# oled_block.net
KiCad netlist of a schematic drawn in EAGLE
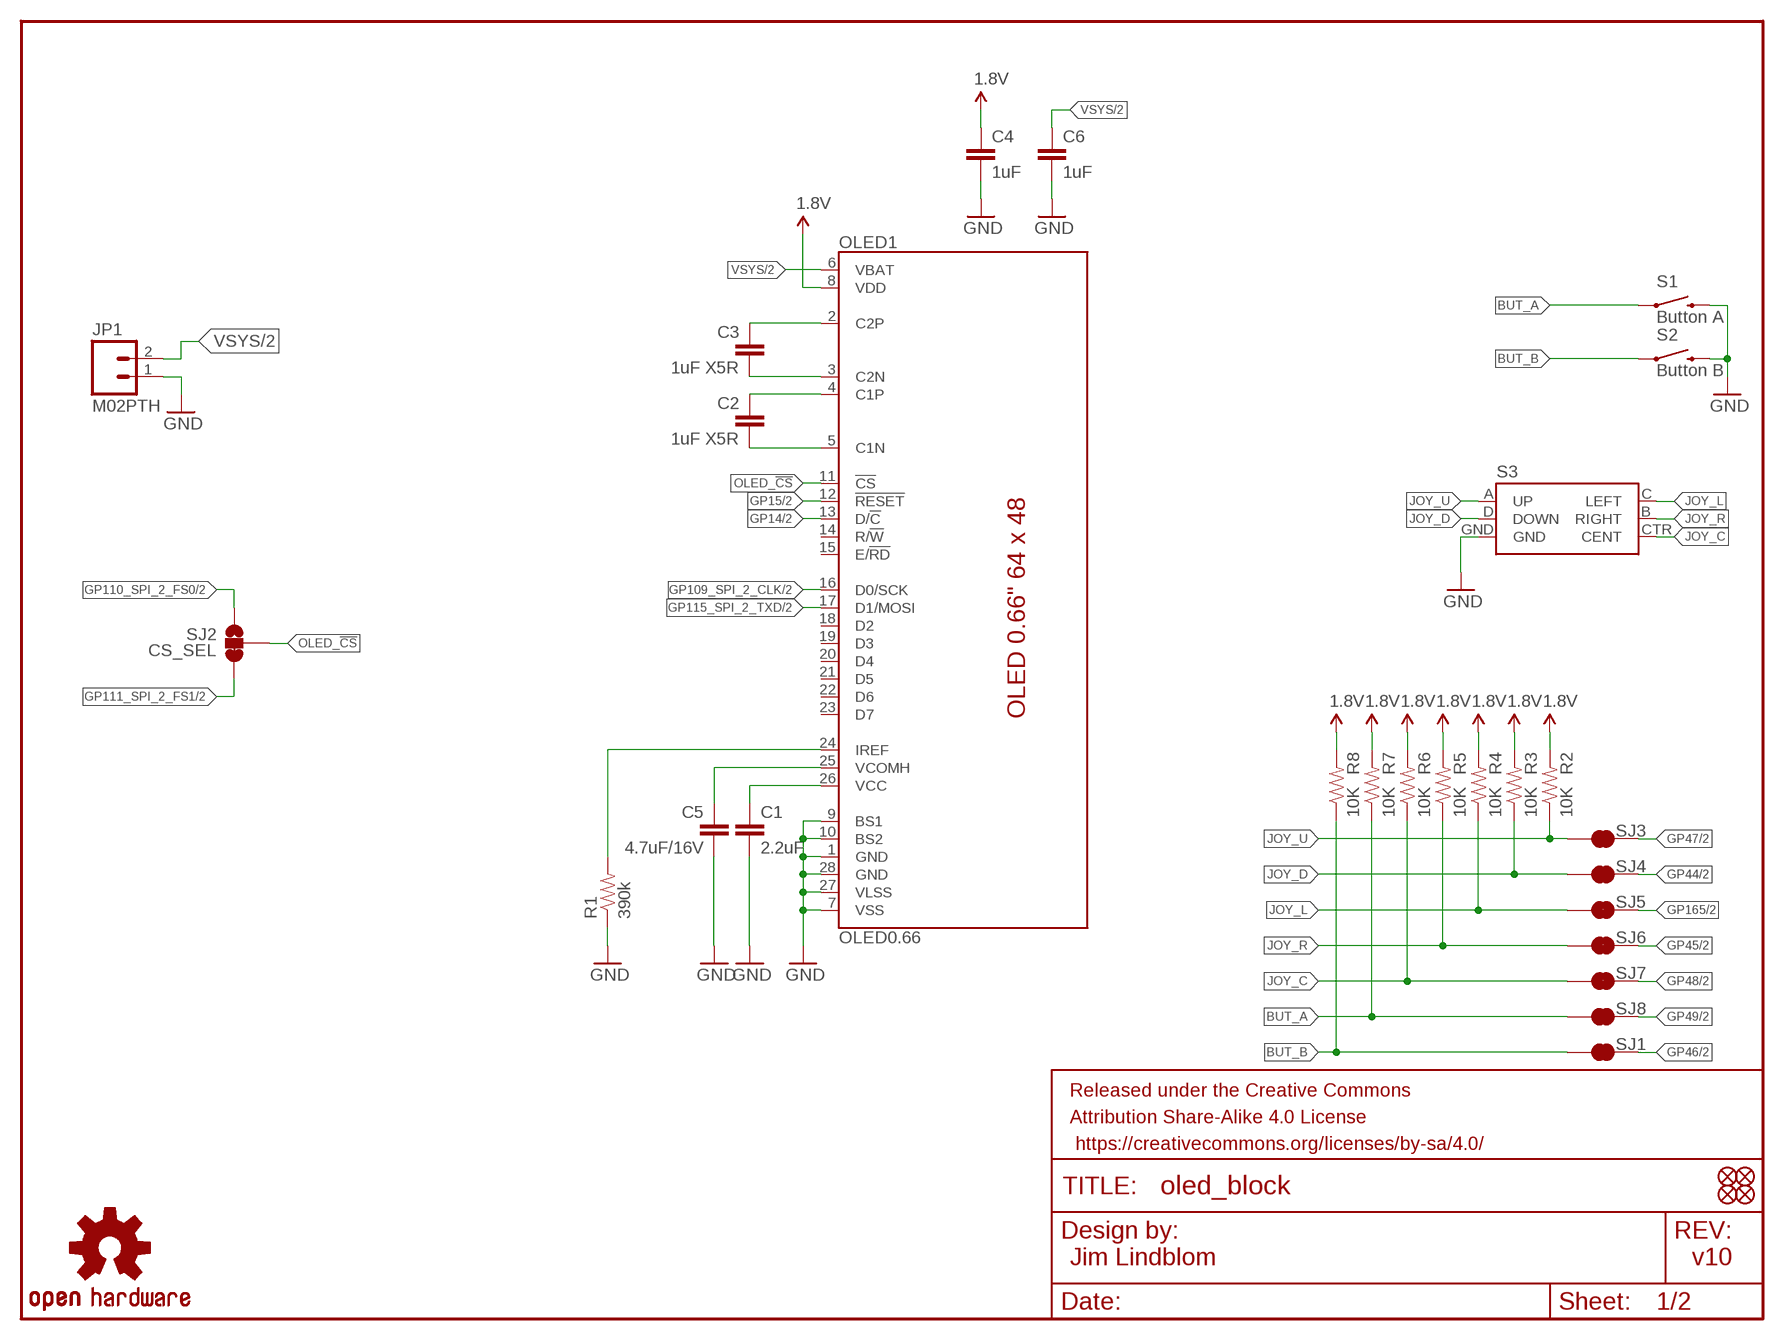
[diagram p0: schematic, sheet 1]
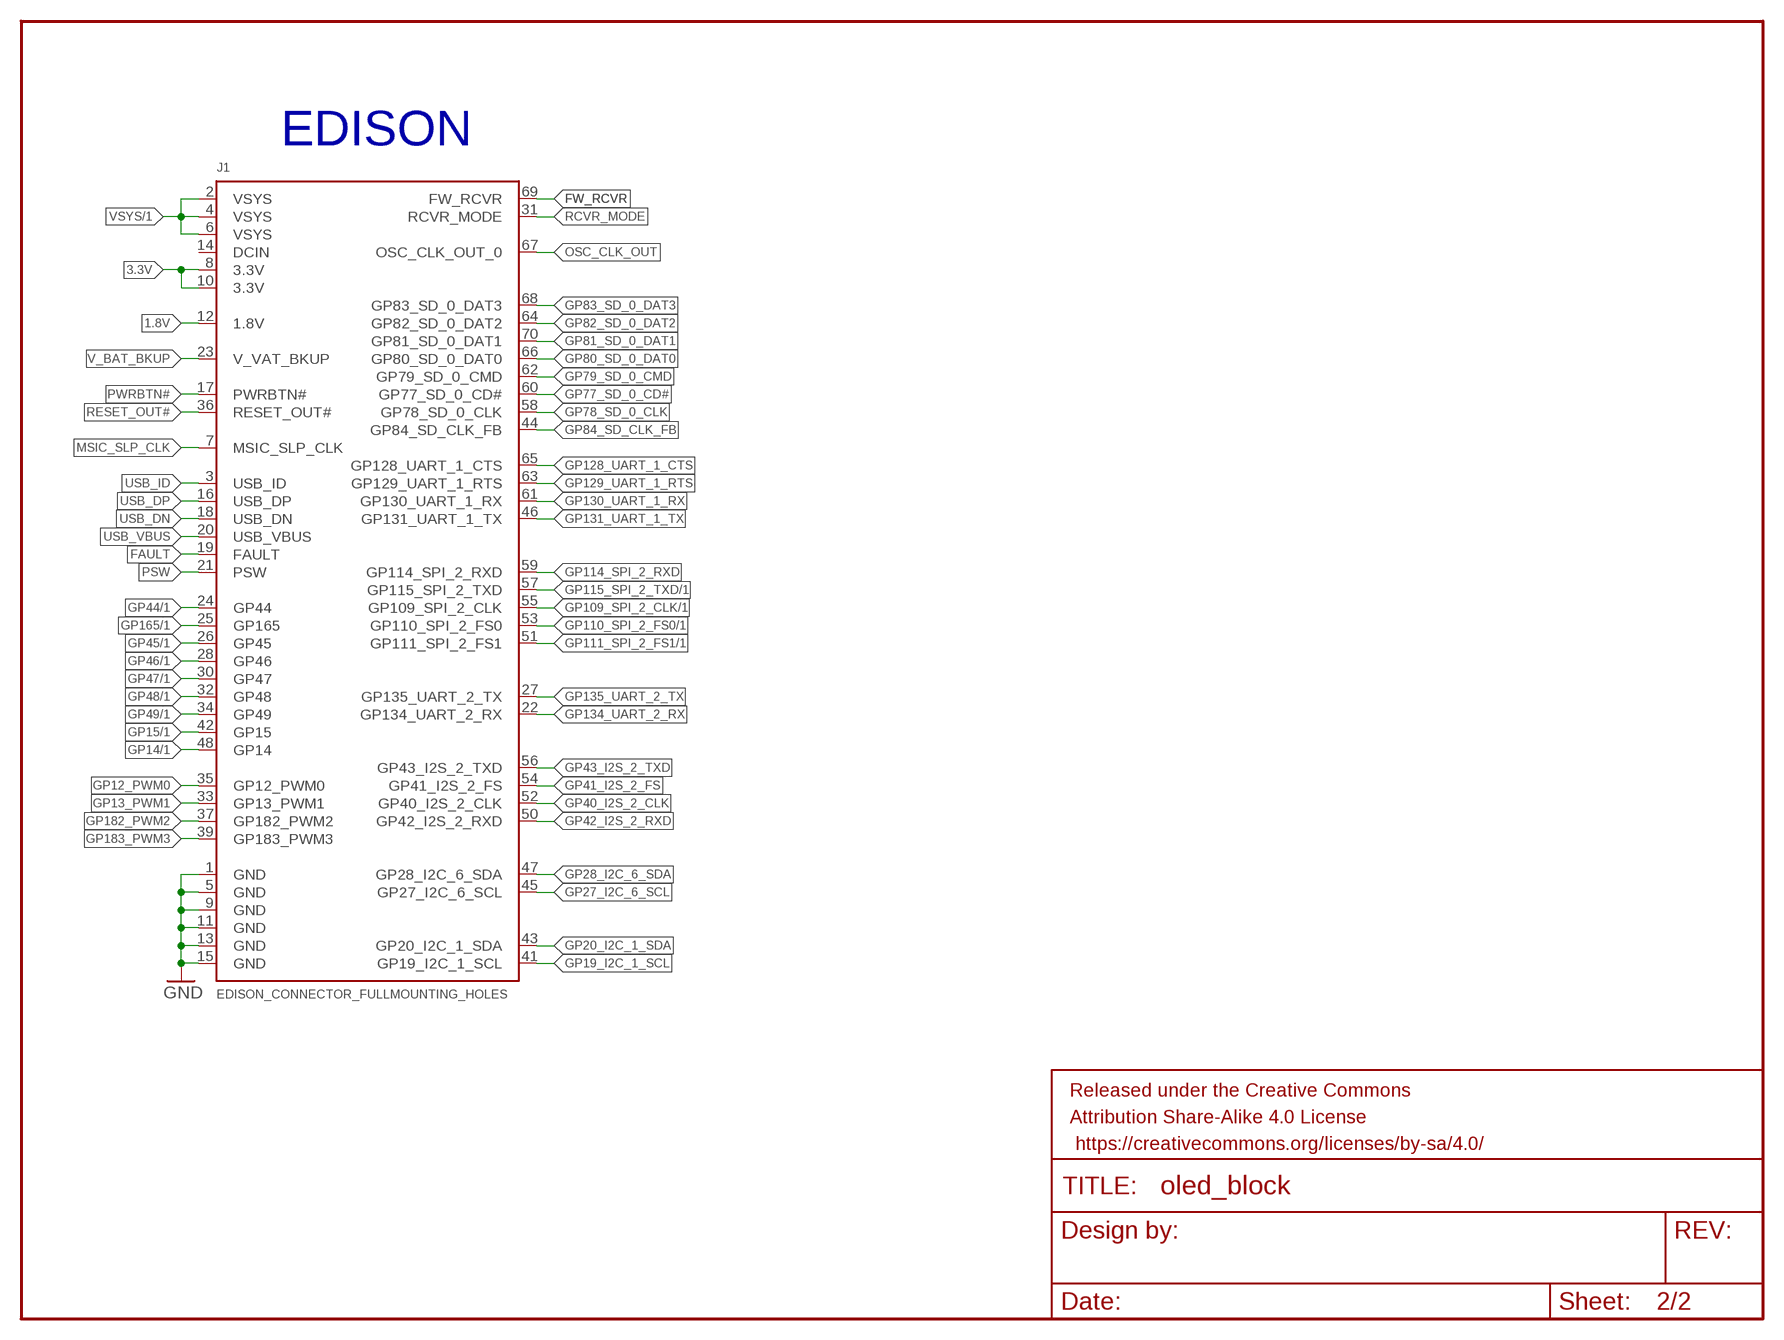
[diagram p1: schematic, sheet 2]

(export (version "E")
  (design (tool "Eeschema 10.0.6"))
  (components
    (comp (ref "C1")
      (value "2.2uF")
      (footprint "eagle-import:0805")
      (libsource (lib "eagle-import") (part "CAP0805"))
    )
    (comp (ref "C2")
      (value "1uF X5R")
      (footprint "eagle-import:0805")
      (libsource (lib "eagle-import") (part "CAP0805"))
    )
    (comp (ref "C3")
      (value "1uF X5R")
      (footprint "eagle-import:0805")
      (libsource (lib "eagle-import") (part "CAP0805"))
    )
    (comp (ref "C4")
      (value "1uF")
      (footprint "eagle-import:0603-CAP")
      (libsource (lib "eagle-import") (part "CAP0603-CAP"))
    )
    (comp (ref "C5")
      (value "4.7uF/16V")
      (footprint "eagle-import:1206")
      (libsource (lib "eagle-import") (part "CAP1206"))
    )
    (comp (ref "C6")
      (value "1uF")
      (footprint "eagle-import:0603-CAP")
      (libsource (lib "eagle-import") (part "CAP0603-CAP"))
    )
    (comp (ref "FID1")
      (value "FIDUCIAL1X2")
      (footprint "eagle-import:FIDUCIAL-1X2")
      (libsource (lib "eagle-import") (part "FIDUCIAL1X2"))
    )
    (comp (ref "FID2")
      (value "FIDUCIAL1X2")
      (footprint "eagle-import:FIDUCIAL-1X2")
      (libsource (lib "eagle-import") (part "FIDUCIAL1X2"))
    )
    (comp (ref "FID3")
      (value "FIDUCIAL1X2")
      (footprint "eagle-import:FIDUCIAL-1X2")
      (libsource (lib "eagle-import") (part "FIDUCIAL1X2"))
    )
    (comp (ref "FID4")
      (value "FIDUCIAL1X2")
      (footprint "eagle-import:FIDUCIAL-1X2")
      (libsource (lib "eagle-import") (part "FIDUCIAL1X2"))
    )
    (comp (ref "FRAME1")
      (value "FRAME-LETTER")
      (footprint "eagle-import:CREATIVE_COMMONS")
      (libsource (lib "eagle-import") (part "FRAME-LETTER"))
    )
    (comp (ref "JP1")
      (value "M02PTH")
      (footprint "eagle-import:1X02")
      (libsource (lib "eagle-import") (part "M02PTH"))
    )
    (comp (ref "LOGO2")
      (value "OSHW-LOGOS")
      (footprint "eagle-import:OSHW-LOGO-S")
      (libsource (lib "eagle-import") (part "OSHW-LOGOS"))
    )
    (comp (ref "OLED1")
      (value "OLED0.66")
      (footprint "eagle-import:OLED-0.66-64X48")
      (libsource (lib "eagle-import") (part "OLED0.66"))
    )
    (comp (ref "R1")
      (value "390k")
      (footprint "eagle-import:0603-RES")
      (libsource (lib "eagle-import") (part "RESISTOR0603-RES"))
    )
    (comp (ref "R2")
      (value "10K")
      (footprint "eagle-import:0603-RES")
      (libsource (lib "eagle-import") (part "10KOHM1/10W1%(0603)0603"))
    )
    (comp (ref "R3")
      (value "10K")
      (footprint "eagle-import:0603-RES")
      (libsource (lib "eagle-import") (part "10KOHM1/10W1%(0603)0603"))
    )
    (comp (ref "R4")
      (value "10K")
      (footprint "eagle-import:0603-RES")
      (libsource (lib "eagle-import") (part "10KOHM1/10W1%(0603)0603"))
    )
    (comp (ref "R5")
      (value "10K")
      (footprint "eagle-import:0603-RES")
      (libsource (lib "eagle-import") (part "10KOHM1/10W1%(0603)0603"))
    )
    (comp (ref "R6")
      (value "10K")
      (footprint "eagle-import:0603-RES")
      (libsource (lib "eagle-import") (part "10KOHM1/10W1%(0603)0603"))
    )
    (comp (ref "R7")
      (value "10K")
      (footprint "eagle-import:0603-RES")
      (libsource (lib "eagle-import") (part "10KOHM1/10W1%(0603)0603"))
    )
    (comp (ref "R8")
      (value "10K")
      (footprint "eagle-import:0603-RES")
      (libsource (lib "eagle-import") (part "10KOHM1/10W1%(0603)0603"))
    )
    (comp (ref "S1")
      (value "Button A")
      (footprint "eagle-import:TACTILE_SWITCH_TALL")
      (libsource (lib "eagle-import") (part "SWITCH-MOMENTARY-2SMD-4"))
    )
    (comp (ref "S2")
      (value "Button B")
      (footprint "eagle-import:TACTILE_SWITCH_TALL")
      (libsource (lib "eagle-import") (part "SWITCH-MOMENTARY-2SMD-4"))
    )
    (comp (ref "S3")
      (value "JOYSTICK_MINI")
      (footprint "eagle-import:JOYSTICK_MINI")
      (libsource (lib "eagle-import") (part "JOYSTICK_MINI"))
    )
    (comp (ref "SJ1")
      (value "JUMPER-PAD-2-NC_BY_TRACE")
      (footprint "eagle-import:PAD-JUMPER-2-NC_BY_TRACE_YES_SILK")
      (libsource (lib "eagle-import") (part "JUMPER-PAD-2-NC_BY_TRACE"))
    )
    (comp (ref "SJ2")
      (value "CS_SEL")
      (footprint "eagle-import:PAD-JUMPER-3-2OF3_NC_BY_TRACE_YES_SILK_FULL_BOX")
      (libsource (lib "eagle-import") (part "JUMPER-PAD-3-2OF3_NC_BY_TRACE"))
    )
    (comp (ref "SJ3")
      (value "JUMPER-PAD-2-NC_BY_TRACE")
      (footprint "eagle-import:PAD-JUMPER-2-NC_BY_TRACE_YES_SILK")
      (libsource (lib "eagle-import") (part "JUMPER-PAD-2-NC_BY_TRACE"))
    )
    (comp (ref "SJ4")
      (value "JUMPER-PAD-2-NC_BY_TRACE")
      (footprint "eagle-import:PAD-JUMPER-2-NC_BY_TRACE_YES_SILK")
      (libsource (lib "eagle-import") (part "JUMPER-PAD-2-NC_BY_TRACE"))
    )
    (comp (ref "SJ5")
      (value "JUMPER-PAD-2-NC_BY_TRACE")
      (footprint "eagle-import:PAD-JUMPER-2-NC_BY_TRACE_YES_SILK")
      (libsource (lib "eagle-import") (part "JUMPER-PAD-2-NC_BY_TRACE"))
    )
    (comp (ref "SJ6")
      (value "JUMPER-PAD-2-NC_BY_TRACE")
      (footprint "eagle-import:PAD-JUMPER-2-NC_BY_TRACE_YES_SILK")
      (libsource (lib "eagle-import") (part "JUMPER-PAD-2-NC_BY_TRACE"))
    )
    (comp (ref "SJ7")
      (value "JUMPER-PAD-2-NC_BY_TRACE")
      (footprint "eagle-import:PAD-JUMPER-2-NC_BY_TRACE_YES_SILK")
      (libsource (lib "eagle-import") (part "JUMPER-PAD-2-NC_BY_TRACE"))
    )
    (comp (ref "SJ8")
      (value "JUMPER-PAD-2-NC_BY_TRACE")
      (footprint "eagle-import:PAD-JUMPER-2-NC_BY_TRACE_YES_SILK")
      (libsource (lib "eagle-import") (part "JUMPER-PAD-2-NC_BY_TRACE"))
    )
    (comp (ref "FRAME2")
      (value "FRAME-LETTER")
      (footprint "eagle-import:CREATIVE_COMMONS")
      (libsource (lib "eagle-import") (part "FRAME-LETTER"))
    )
    (comp (ref "J1")
      (value "EDISON_CONNECTOR_FULLMOUNTING_HOLES")
      (footprint "eagle-import:EDISON_DAUGHTER")
      (libsource (lib "eagle-import") (part "EDISON_CONNECTOR_FULLMOUNTING_HOLES"))
    )
  )
  (nets
    (net (code "1") (name "1.8V") (class "Default")
      (node (ref "C4") (pin "1") (pinfunction "1_1") (pintype "passive"))
      (node (ref "J1") (pin "12") (pinfunction "1.8V_12") (pintype "bidirectional"))
      (node (ref "OLED1") (pin "8") (pinfunction "VDD_8") (pintype "bidirectional"))
      (node (ref "R2") (pin "2") (pinfunction "2_2") (pintype "passive"))
      (node (ref "R3") (pin "2") (pinfunction "2_2") (pintype "passive"))
      (node (ref "R4") (pin "2") (pinfunction "2_2") (pintype "passive"))
      (node (ref "R5") (pin "2") (pinfunction "2_2") (pintype "passive"))
      (node (ref "R6") (pin "2") (pinfunction "2_2") (pintype "passive"))
      (node (ref "R7") (pin "2") (pinfunction "2_2") (pintype "passive"))
      (node (ref "R8") (pin "2") (pinfunction "2_2") (pintype "passive"))
    )
    (net (code "2") (name "3.3V") (class "Default")
      (node (ref "J1") (pin "10") (pinfunction "3.3V_10") (pintype "bidirectional"))
      (node (ref "J1") (pin "8") (pinfunction "3.3V_8") (pintype "bidirectional"))
    )
    (net (code "3") (name "BUT_A") (class "Default")
      (node (ref "R7") (pin "1") (pinfunction "1_1") (pintype "passive"))
      (node (ref "S1") (pin "A2") (pinfunction "1_A2") (pintype "passive"))
      (node (ref "SJ8") (pin "1") (pinfunction "1_1") (pintype "passive"))
    )
    (net (code "4") (name "BUT_B") (class "Default")
      (node (ref "R8") (pin "1") (pinfunction "1_1") (pintype "passive"))
      (node (ref "S2") (pin "A2") (pinfunction "1_A2") (pintype "passive"))
      (node (ref "SJ1") (pin "1") (pinfunction "1_1") (pintype "passive"))
    )
    (net (code "5") (name "FAULT") (class "Default")
      (node (ref "J1") (pin "19") (pinfunction "FAULT_19") (pintype "bidirectional"))
    )
    (net (code "6") (name "FW_RCVR") (class "Default")
      (node (ref "J1") (pin "69") (pinfunction "FW_RCVR_69") (pintype "bidirectional"))
    )
    (net (code "7") (name "GND") (class "Default")
      (node (ref "C1") (pin "2") (pinfunction "2_2") (pintype "passive"))
      (node (ref "C4") (pin "2") (pinfunction "2_2") (pintype "passive"))
      (node (ref "C5") (pin "2") (pinfunction "2_2") (pintype "passive"))
      (node (ref "C6") (pin "2") (pinfunction "2_2") (pintype "passive"))
      (node (ref "J1") (pin "1") (pinfunction "GND_1") (pintype "bidirectional"))
      (node (ref "J1") (pin "11") (pinfunction "GND_11") (pintype "bidirectional"))
      (node (ref "J1") (pin "13") (pinfunction "GND_13") (pintype "bidirectional"))
      (node (ref "J1") (pin "15") (pinfunction "GND_15") (pintype "bidirectional"))
      (node (ref "J1") (pin "5") (pinfunction "GND_5") (pintype "bidirectional"))
      (node (ref "J1") (pin "9") (pinfunction "GND_9") (pintype "bidirectional"))
      (node (ref "JP1") (pin "1") (pinfunction "1_1") (pintype "passive"))
      (node (ref "OLED1") (pin "1") (pinfunction "GND_1") (pintype "bidirectional"))
      (node (ref "OLED1") (pin "10") (pinfunction "BS2_10") (pintype "bidirectional"))
      (node (ref "OLED1") (pin "27") (pinfunction "VLSS_27") (pintype "bidirectional"))
      (node (ref "OLED1") (pin "28") (pinfunction "GND_28") (pintype "bidirectional"))
      (node (ref "OLED1") (pin "7") (pinfunction "VSS_7") (pintype "bidirectional"))
      (node (ref "OLED1") (pin "9") (pinfunction "BS1_9") (pintype "bidirectional"))
      (node (ref "R1") (pin "1") (pinfunction "1_1") (pintype "passive"))
      (node (ref "S1") (pin "B2") (pinfunction "2_B2") (pintype "passive"))
      (node (ref "S2") (pin "B2") (pinfunction "2_B2") (pintype "passive"))
      (node (ref "S3") (pin "GND") (pinfunction "GND_GND") (pintype "bidirectional"))
    )
    (net (code "8") (name "GP12_PWM0") (class "Default")
      (node (ref "J1") (pin "35") (pinfunction "GP12_PWM0_35") (pintype "bidirectional"))
    )
    (net (code "9") (name "GP13_PWM1") (class "Default")
      (node (ref "J1") (pin "33") (pinfunction "GP13_PWM1_33") (pintype "bidirectional"))
    )
    (net (code "10") (name "GP14") (class "Default")
      (node (ref "J1") (pin "48") (pinfunction "GP14_48") (pintype "bidirectional"))
      (node (ref "OLED1") (pin "13") (pinfunction "D/~{C}_13") (pintype "bidirectional"))
    )
    (net (code "11") (name "GP15") (class "Default")
      (node (ref "J1") (pin "42") (pinfunction "GP15_42") (pintype "bidirectional"))
      (node (ref "OLED1") (pin "12") (pinfunction "~{RESET}_12") (pintype "bidirectional"))
    )
    (net (code "12") (name "GP19_I2C_1_SCL") (class "Default")
      (node (ref "J1") (pin "41") (pinfunction "GP19_I2C_1_SCL_41") (pintype "bidirectional"))
    )
    (net (code "13") (name "GP20_I2C_1_SDA") (class "Default")
      (node (ref "J1") (pin "43") (pinfunction "GP20_I2C_1_SDA_43") (pintype "bidirectional"))
    )
    (net (code "14") (name "GP27_I2C_6_SCL") (class "Default")
      (node (ref "J1") (pin "45") (pinfunction "GP27_I2C_6_SCL_45") (pintype "bidirectional"))
    )
    (net (code "15") (name "GP28_I2C_6_SDA") (class "Default")
      (node (ref "J1") (pin "47") (pinfunction "GP28_I2C_6_SDA_47") (pintype "bidirectional"))
    )
    (net (code "16") (name "GP40_I2S_2_CLK") (class "Default")
      (node (ref "J1") (pin "52") (pinfunction "GP40_I2S_2_CLK_52") (pintype "bidirectional"))
    )
    (net (code "17") (name "GP41_I2S_2_FS") (class "Default")
      (node (ref "J1") (pin "54") (pinfunction "GP41_I2S_2_FS_54") (pintype "bidirectional"))
    )
    (net (code "18") (name "GP42_I2S_2_RXD") (class "Default")
      (node (ref "J1") (pin "50") (pinfunction "GP42_I2S_2_RXD_50") (pintype "bidirectional"))
    )
    (net (code "19") (name "GP43_I2S_2_TXD") (class "Default")
      (node (ref "J1") (pin "56") (pinfunction "GP43_I2S_2_TXD_56") (pintype "bidirectional"))
    )
    (net (code "20") (name "GP44") (class "Default")
      (node (ref "J1") (pin "24") (pinfunction "GP44_24") (pintype "bidirectional"))
      (node (ref "SJ4") (pin "2") (pinfunction "2_2") (pintype "passive"))
    )
    (net (code "21") (name "GP45") (class "Default")
      (node (ref "J1") (pin "26") (pinfunction "GP45_26") (pintype "bidirectional"))
      (node (ref "SJ6") (pin "2") (pinfunction "2_2") (pintype "passive"))
    )
    (net (code "22") (name "GP46") (class "Default")
      (node (ref "J1") (pin "28") (pinfunction "GP46_28") (pintype "bidirectional"))
      (node (ref "SJ1") (pin "2") (pinfunction "2_2") (pintype "passive"))
    )
    (net (code "23") (name "GP47") (class "Default")
      (node (ref "J1") (pin "30") (pinfunction "GP47_30") (pintype "bidirectional"))
      (node (ref "SJ3") (pin "2") (pinfunction "2_2") (pintype "passive"))
    )
    (net (code "24") (name "GP48") (class "Default")
      (node (ref "J1") (pin "32") (pinfunction "GP48_32") (pintype "bidirectional"))
      (node (ref "SJ7") (pin "2") (pinfunction "2_2") (pintype "passive"))
    )
    (net (code "25") (name "GP49") (class "Default")
      (node (ref "J1") (pin "34") (pinfunction "GP49_34") (pintype "bidirectional"))
      (node (ref "SJ8") (pin "2") (pinfunction "2_2") (pintype "passive"))
    )
    (net (code "26") (name "GP77_SD_0_CD#") (class "Default")
      (node (ref "J1") (pin "60") (pinfunction "GP77_SD_0_CD#_60") (pintype "bidirectional"))
    )
    (net (code "27") (name "GP78_SD_0_CLK") (class "Default")
      (node (ref "J1") (pin "58") (pinfunction "GP78_SD_0_CLK_58") (pintype "bidirectional"))
    )
    (net (code "28") (name "GP79_SD_0_CMD") (class "Default")
      (node (ref "J1") (pin "62") (pinfunction "GP79_SD_0_CMD_62") (pintype "bidirectional"))
    )
    (net (code "29") (name "GP80_SD_0_DAT0") (class "Default")
      (node (ref "J1") (pin "66") (pinfunction "GP80_SD_0_DAT0_66") (pintype "bidirectional"))
    )
    (net (code "30") (name "GP81_SD_0_DAT1") (class "Default")
      (node (ref "J1") (pin "70") (pinfunction "GP81_SD_0_DAT1_70") (pintype "bidirectional"))
    )
    (net (code "31") (name "GP82_SD_0_DAT2") (class "Default")
      (node (ref "J1") (pin "64") (pinfunction "GP82_SD_0_DAT2_64") (pintype "bidirectional"))
    )
    (net (code "32") (name "GP83_SD_0_DAT3") (class "Default")
      (node (ref "J1") (pin "68") (pinfunction "GP83_SD_0_DAT3_68") (pintype "bidirectional"))
    )
    (net (code "33") (name "GP84_SD_CLK_FB") (class "Default")
      (node (ref "J1") (pin "44") (pinfunction "GP84_SD_CLK_FB_44") (pintype "bidirectional"))
    )
    (net (code "34") (name "GP109_SPI_2_CLK") (class "Default")
      (node (ref "J1") (pin "55") (pinfunction "GP109_SPI_2_CLK_55") (pintype "bidirectional"))
      (node (ref "OLED1") (pin "16") (pinfunction "D0/SCK_16") (pintype "bidirectional"))
    )
    (net (code "35") (name "GP110_SPI_2_FS0") (class "Default")
      (node (ref "J1") (pin "53") (pinfunction "GP110_SPI_2_FS0_53") (pintype "bidirectional"))
      (node (ref "SJ2") (pin "1") (pinfunction "1_1") (pintype "passive"))
    )
    (net (code "36") (name "GP111_SPI_2_FS1") (class "Default")
      (node (ref "J1") (pin "51") (pinfunction "GP111_SPI_2_FS1_51") (pintype "bidirectional"))
      (node (ref "SJ2") (pin "3") (pinfunction "3_3") (pintype "passive"))
    )
    (net (code "37") (name "GP114_SPI_2_RXD") (class "Default")
      (node (ref "J1") (pin "59") (pinfunction "GP114_SPI_2_RXD_59") (pintype "bidirectional"))
    )
    (net (code "38") (name "GP115_SPI_2_TXD") (class "Default")
      (node (ref "J1") (pin "57") (pinfunction "GP115_SPI_2_TXD_57") (pintype "bidirectional"))
      (node (ref "OLED1") (pin "17") (pinfunction "D1/MOSI_17") (pintype "bidirectional"))
    )
    (net (code "39") (name "GP128_UART_1_CTS") (class "Default")
      (node (ref "J1") (pin "65") (pinfunction "GP128_UART_1_CTS_65") (pintype "bidirectional"))
    )
    (net (code "40") (name "GP129_UART_1_RTS") (class "Default")
      (node (ref "J1") (pin "63") (pinfunction "GP129_UART_1_RTS_63") (pintype "bidirectional"))
    )
    (net (code "41") (name "GP130_UART_1_RX") (class "Default")
      (node (ref "J1") (pin "61") (pinfunction "GP130_UART_1_RX_61") (pintype "bidirectional"))
    )
    (net (code "42") (name "GP131_UART_1_TX") (class "Default")
      (node (ref "J1") (pin "46") (pinfunction "GP131_UART_1_TX_46") (pintype "bidirectional"))
    )
    (net (code "43") (name "GP134_UART_2_RX") (class "Default")
      (node (ref "J1") (pin "22") (pinfunction "GP134_UART_2_RX_22") (pintype "bidirectional"))
    )
    (net (code "44") (name "GP135_UART_2_TX") (class "Default")
      (node (ref "J1") (pin "27") (pinfunction "GP135_UART_2_TX_27") (pintype "bidirectional"))
    )
    (net (code "45") (name "GP165") (class "Default")
      (node (ref "J1") (pin "25") (pinfunction "GP165_25") (pintype "bidirectional"))
      (node (ref "SJ5") (pin "2") (pinfunction "2_2") (pintype "passive"))
    )
    (net (code "46") (name "GP182_PWM2") (class "Default")
      (node (ref "J1") (pin "37") (pinfunction "GP182_PWM2_37") (pintype "bidirectional"))
    )
    (net (code "47") (name "GP183_PWM3") (class "Default")
      (node (ref "J1") (pin "39") (pinfunction "GP183_PWM3_39") (pintype "bidirectional"))
    )
    (net (code "48") (name "JOY_C") (class "Default")
      (node (ref "R6") (pin "1") (pinfunction "1_1") (pintype "passive"))
      (node (ref "S3") (pin "CTR") (pinfunction "CENT_CTR") (pintype "bidirectional"))
      (node (ref "SJ7") (pin "1") (pinfunction "1_1") (pintype "passive"))
    )
    (net (code "49") (name "JOY_D") (class "Default")
      (node (ref "R3") (pin "1") (pinfunction "1_1") (pintype "passive"))
      (node (ref "S3") (pin "D") (pinfunction "DOWN_D") (pintype "bidirectional"))
      (node (ref "SJ4") (pin "1") (pinfunction "1_1") (pintype "passive"))
    )
    (net (code "50") (name "JOY_L") (class "Default")
      (node (ref "R4") (pin "1") (pinfunction "1_1") (pintype "passive"))
      (node (ref "S3") (pin "C") (pinfunction "LEFT_C") (pintype "bidirectional"))
      (node (ref "SJ5") (pin "1") (pinfunction "1_1") (pintype "passive"))
    )
    (net (code "51") (name "JOY_R") (class "Default")
      (node (ref "R5") (pin "1") (pinfunction "1_1") (pintype "passive"))
      (node (ref "S3") (pin "B") (pinfunction "RIGHT_B") (pintype "bidirectional"))
      (node (ref "SJ6") (pin "1") (pinfunction "1_1") (pintype "passive"))
    )
    (net (code "52") (name "JOY_U") (class "Default")
      (node (ref "R2") (pin "1") (pinfunction "1_1") (pintype "passive"))
      (node (ref "S3") (pin "A") (pinfunction "UP_A") (pintype "bidirectional"))
      (node (ref "SJ3") (pin "1") (pinfunction "1_1") (pintype "passive"))
    )
    (net (code "53") (name "MSIC_SLP_CLK") (class "Default")
      (node (ref "J1") (pin "7") (pinfunction "MSIC_SLP_CLK_7") (pintype "bidirectional"))
    )
    (net (code "54") (name "Net-(OLED1-C1N)") (class "Default")
      (node (ref "C2") (pin "2") (pinfunction "2_2") (pintype "passive"))
      (node (ref "OLED1") (pin "5") (pinfunction "C1N_5") (pintype "bidirectional"))
    )
    (net (code "55") (name "Net-(OLED1-C1P)") (class "Default")
      (node (ref "C2") (pin "1") (pinfunction "1_1") (pintype "passive"))
      (node (ref "OLED1") (pin "4") (pinfunction "C1P_4") (pintype "bidirectional"))
    )
    (net (code "56") (name "Net-(OLED1-C2N)") (class "Default")
      (node (ref "C3") (pin "2") (pinfunction "2_2") (pintype "passive"))
      (node (ref "OLED1") (pin "3") (pinfunction "C2N_3") (pintype "bidirectional"))
    )
    (net (code "57") (name "Net-(OLED1-C2P)") (class "Default")
      (node (ref "C3") (pin "1") (pinfunction "1_1") (pintype "passive"))
      (node (ref "OLED1") (pin "2") (pinfunction "C2P_2") (pintype "bidirectional"))
    )
    (net (code "58") (name "Net-(OLED1-IREF)") (class "Default")
      (node (ref "OLED1") (pin "24") (pinfunction "IREF_24") (pintype "bidirectional"))
      (node (ref "R1") (pin "2") (pinfunction "2_2") (pintype "passive"))
    )
    (net (code "59") (name "Net-(OLED1-VCC)") (class "Default")
      (node (ref "C1") (pin "1") (pinfunction "1_1") (pintype "passive"))
      (node (ref "OLED1") (pin "26") (pinfunction "VCC_26") (pintype "bidirectional"))
    )
    (net (code "60") (name "Net-(OLED1-VCOMH)") (class "Default")
      (node (ref "C5") (pin "1") (pinfunction "1_1") (pintype "passive"))
      (node (ref "OLED1") (pin "25") (pinfunction "VCOMH_25") (pintype "bidirectional"))
    )
    (net (code "61") (name "OLED_~{CS}") (class "Default")
      (node (ref "OLED1") (pin "11") (pinfunction "~{CS}_11") (pintype "bidirectional"))
      (node (ref "SJ2") (pin "2") (pinfunction "2_2") (pintype "passive"))
    )
    (net (code "62") (name "OSC_CLK_OUT") (class "Default")
      (node (ref "J1") (pin "67") (pinfunction "OSC_CLK_OUT_0_67") (pintype "bidirectional"))
    )
    (net (code "63") (name "PSW") (class "Default")
      (node (ref "J1") (pin "21") (pinfunction "PSW_21") (pintype "bidirectional"))
    )
    (net (code "64") (name "PWRBTN#") (class "Default")
      (node (ref "J1") (pin "17") (pinfunction "PWRBTN#_17") (pintype "bidirectional"))
    )
    (net (code "65") (name "RCVR_MODE") (class "Default")
      (node (ref "J1") (pin "31") (pinfunction "RCVR_MODE_31") (pintype "bidirectional"))
    )
    (net (code "66") (name "RESET_OUT#") (class "Default")
      (node (ref "J1") (pin "36") (pinfunction "RESET_OUT#_36") (pintype "bidirectional"))
    )
    (net (code "67") (name "USB_DN") (class "Default")
      (node (ref "J1") (pin "18") (pinfunction "USB_DN_18") (pintype "bidirectional"))
    )
    (net (code "68") (name "USB_DP") (class "Default")
      (node (ref "J1") (pin "16") (pinfunction "USB_DP_16") (pintype "bidirectional"))
    )
    (net (code "69") (name "USB_ID") (class "Default")
      (node (ref "J1") (pin "3") (pinfunction "USB_ID_3") (pintype "bidirectional"))
    )
    (net (code "70") (name "USB_VBUS") (class "Default")
      (node (ref "J1") (pin "20") (pinfunction "USB_VBUS_20") (pintype "bidirectional"))
    )
    (net (code "71") (name "VSYS") (class "Default")
      (node (ref "C6") (pin "1") (pinfunction "1_1") (pintype "passive"))
      (node (ref "J1") (pin "2") (pinfunction "VSYS_2") (pintype "bidirectional"))
      (node (ref "J1") (pin "4") (pinfunction "VSYS_4") (pintype "bidirectional"))
      (node (ref "J1") (pin "6") (pinfunction "VSYS_6") (pintype "bidirectional"))
      (node (ref "JP1") (pin "2") (pinfunction "2_2") (pintype "passive"))
      (node (ref "OLED1") (pin "6") (pinfunction "VBAT_6") (pintype "bidirectional"))
    )
    (net (code "72") (name "V_BAT_BKUP") (class "Default")
      (node (ref "J1") (pin "23") (pinfunction "V_VAT_BKUP_23") (pintype "bidirectional"))
    )
    (net (code "73") (name "unconnected-(J1-DCIN-Pad14)") (class "Default")
      (node (ref "J1") (pin "14") (pinfunction "DCIN_14") (pintype "bidirectional"))
    )
    (net (code "74") (name "unconnected-(OLED1-D2-Pad18)") (class "Default")
      (node (ref "OLED1") (pin "18") (pinfunction "D2_18") (pintype "bidirectional"))
    )
    (net (code "75") (name "unconnected-(OLED1-D3-Pad19)") (class "Default")
      (node (ref "OLED1") (pin "19") (pinfunction "D3_19") (pintype "bidirectional"))
    )
    (net (code "76") (name "unconnected-(OLED1-D4-Pad20)") (class "Default")
      (node (ref "OLED1") (pin "20") (pinfunction "D4_20") (pintype "bidirectional"))
    )
    (net (code "77") (name "unconnected-(OLED1-D5-Pad21)") (class "Default")
      (node (ref "OLED1") (pin "21") (pinfunction "D5_21") (pintype "bidirectional"))
    )
    (net (code "78") (name "unconnected-(OLED1-D6-Pad22)") (class "Default")
      (node (ref "OLED1") (pin "22") (pinfunction "D6_22") (pintype "bidirectional"))
    )
    (net (code "79") (name "unconnected-(OLED1-D7-Pad23)") (class "Default")
      (node (ref "OLED1") (pin "23") (pinfunction "D7_23") (pintype "bidirectional"))
    )
    (net (code "80") (name "unconnected-(OLED1-E{slash}~{RD}-Pad15)") (class "Default")
      (node (ref "OLED1") (pin "15") (pinfunction "E/~{RD}_15") (pintype "bidirectional"))
    )
    (net (code "81") (name "unconnected-(OLED1-R{slash}~{W}-Pad14)") (class "Default")
      (node (ref "OLED1") (pin "14") (pinfunction "R/~{W}_14") (pintype "bidirectional"))
    )
  )
)
